# 05_Output_Connectors.net
KiCad netlist of a schematic drawn in Altium Designer
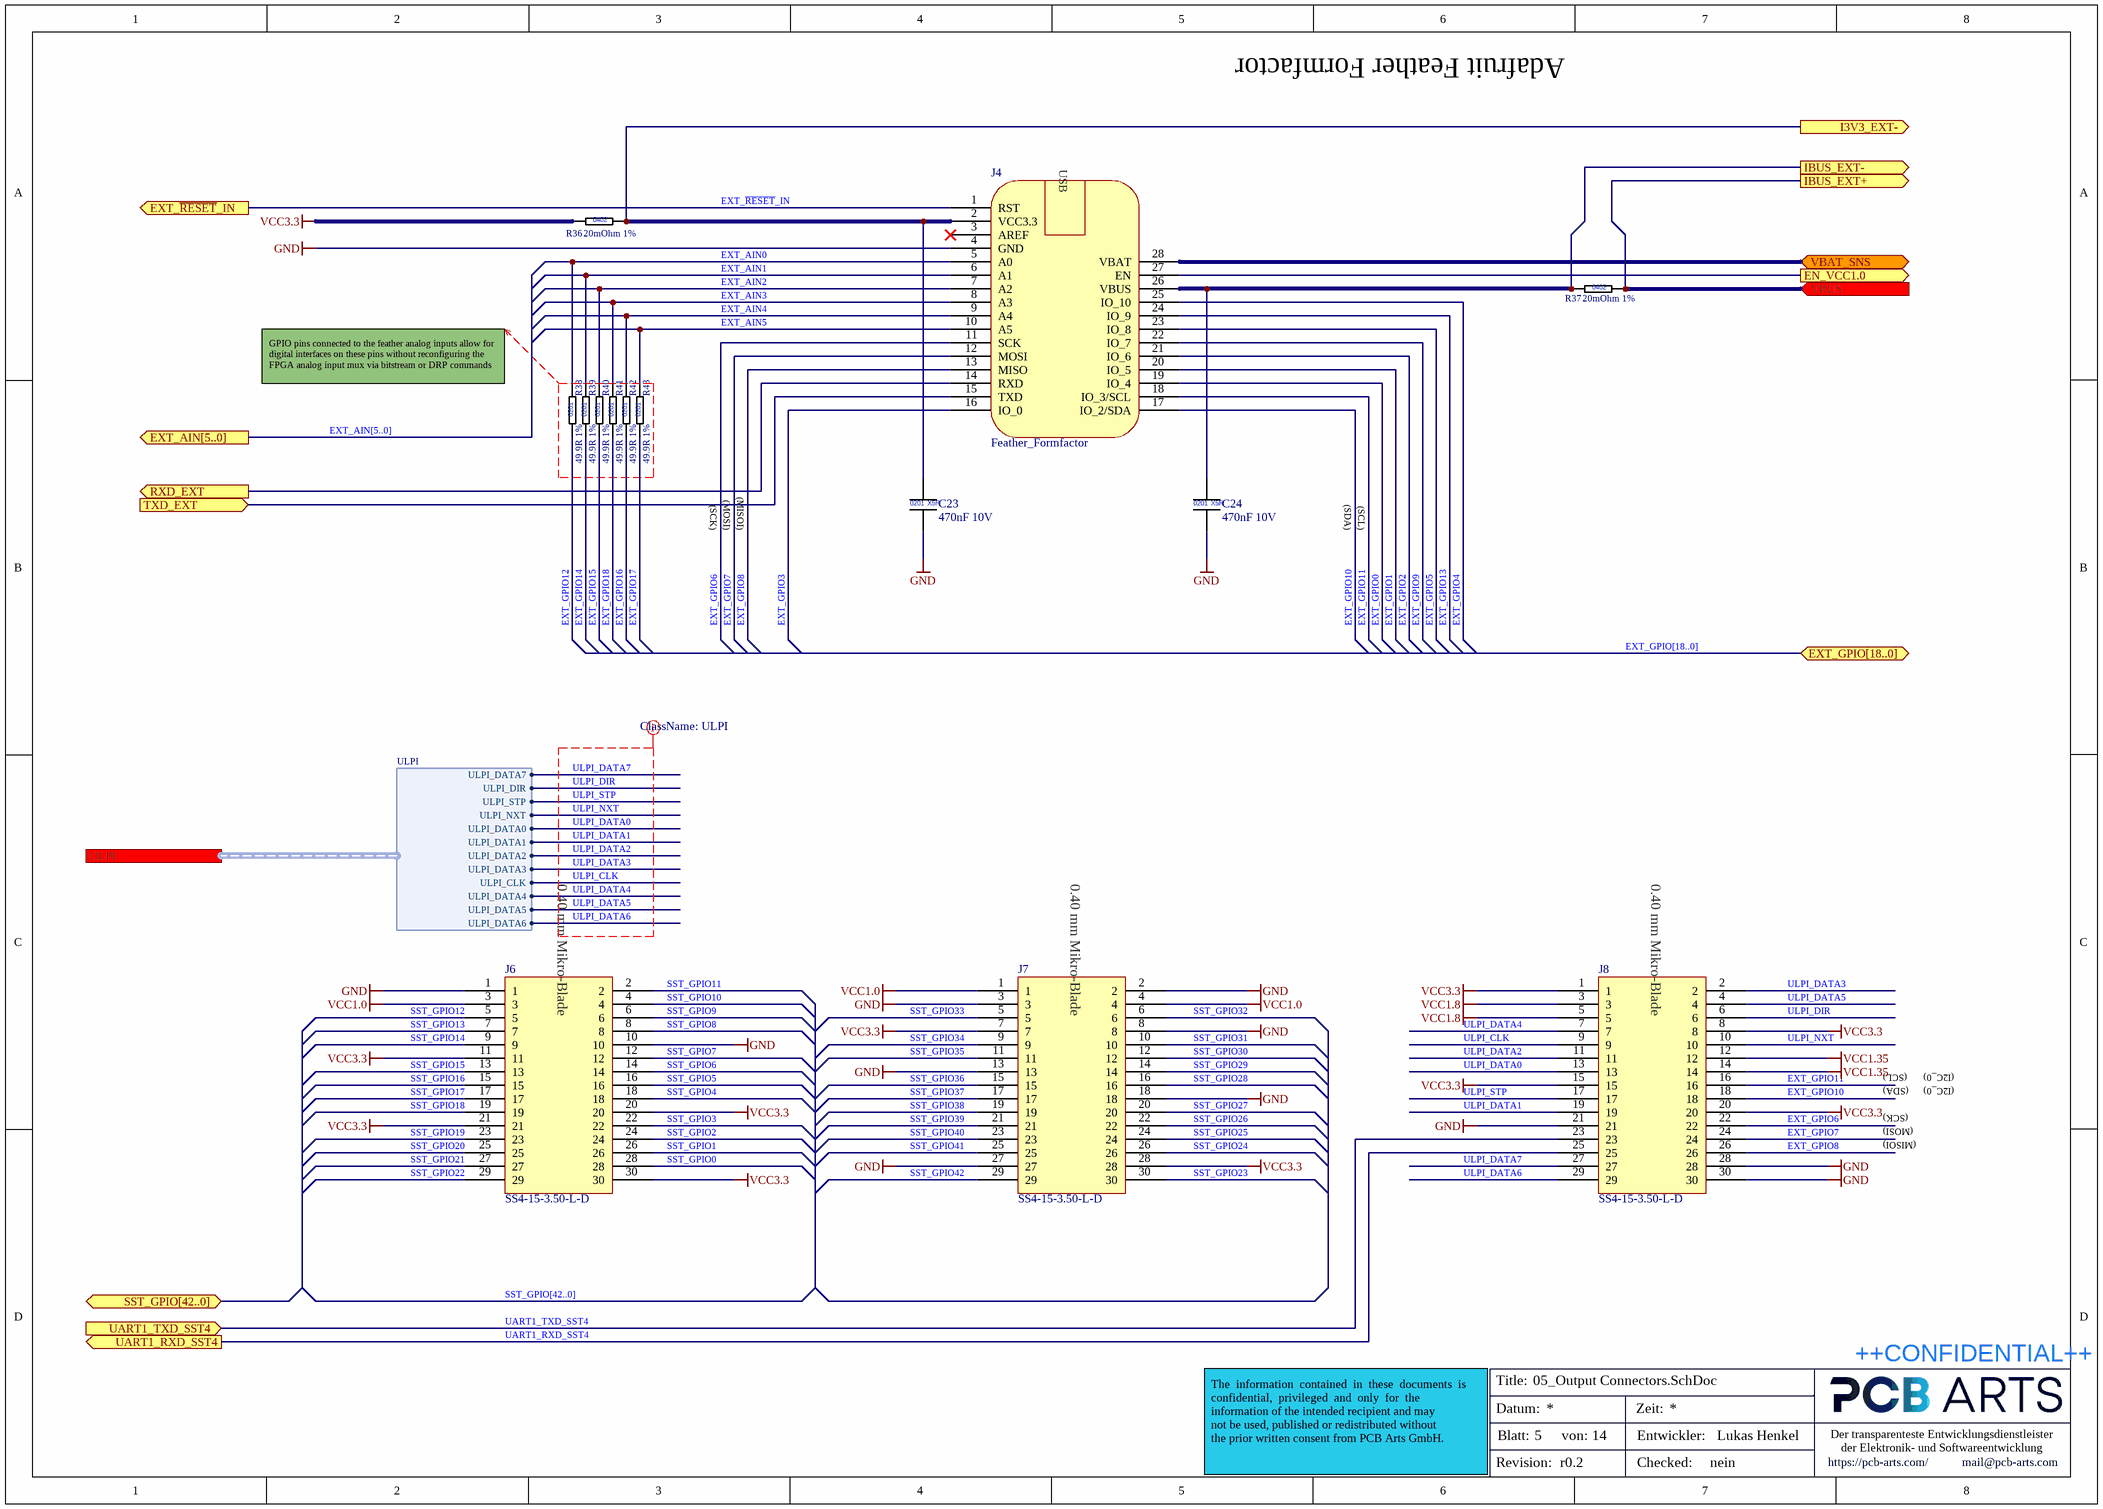
[diagram p0: 05_Output Connectors.SchDoc]

(export (version "E")
  (design (tool "Eeschema 10.0.6"))
  (components
    (comp (ref "C23")
      (value "470nF 10V")
      (footprint "Zynq-Feather-HD:CAPC0603X03L")
      (description "Multilayer Ceramic Capacitors MLCC - SMD/SMT 0201 10VDC")
      (libsource (lib "Zynq-Feather-HD") (part "CAP_0201_470nF_10V"))
    )
    (comp (ref "C24")
      (value "470nF 10V")
      (footprint "Zynq-Feather-HD:CAPC0603X03L")
      (description "Multilayer Ceramic Capacitors MLCC - SMD/SMT 0201 10VDC")
      (libsource (lib "Zynq-Feather-HD") (part "CAP_0201_470nF_10V"))
    )
    (comp (ref "J4")
      (value "Feather_Formfactor")
      (footprint "Zynq-Feather-HD:Feather_FFC")
      (libsource (lib "Zynq-Feather-HD") (part "Feather_Formfactor"))
    )
    (comp (ref "J6")
      (value "SS4-15-3.50-L-D")
      (footprint "Zynq-Feather-HD:SS4-15-3.50-L-D")
      (description "0.40 mm Mikro-Blade & Beam ultrafeine Raster-Stiftleiste")
      (libsource (lib "Zynq-Feather-HD") (part "SS4-15-3.50-L-D_0.40 mm Mikro-Blade & Beam"))
    )
    (comp (ref "J7")
      (value "SS4-15-3.50-L-D")
      (footprint "Zynq-Feather-HD:SS4-15-3.50-L-D")
      (description "0.40 mm Mikro-Blade & Beam ultrafeine Raster-Stiftleiste")
      (libsource (lib "Zynq-Feather-HD") (part "SS4-15-3.50-L-D_0.40 mm Mikro-Blade & Beam"))
    )
    (comp (ref "J8")
      (value "SS4-15-3.50-L-D")
      (footprint "Zynq-Feather-HD:SS4-15-3.50-L-D")
      (description "0.40 mm Mikro-Blade & Beam ultrafeine Raster-Stiftleiste")
      (libsource (lib "Zynq-Feather-HD") (part "SS4-15-3.50-L-D_0.40 mm Mikro-Blade & Beam"))
    )
    (comp (ref "R36")
      (value "20mOhm 1%")
      (footprint "Zynq-Feather-HD:RESC1005X04L")
      (description "Thick Film Resistors - SMD 20mOHM 1%")
      (libsource (lib "Zynq-Feather-HD") (part "RES_0402_20mR_1%"))
    )
    (comp (ref "R37")
      (value "20mOhm 1%")
      (footprint "Zynq-Feather-HD:RESC1005X04L")
      (description "Thick Film Resistors - SMD 20mOHM 1%")
      (libsource (lib "Zynq-Feather-HD") (part "RES_0402_20mR_1%"))
    )
    (comp (ref "R38")
      (value "49.9R 1%")
      (footprint "Zynq-Feather-HD:RESC0603X03L")
      (description "Thick Film Resistors - SMD 49.9R OHM 1%")
      (libsource (lib "Zynq-Feather-HD") (part "RES_0201_49.9R_1%"))
    )
    (comp (ref "R39")
      (value "49.9R 1%")
      (footprint "Zynq-Feather-HD:RESC0603X03L")
      (description "Thick Film Resistors - SMD 49.9R OHM 1%")
      (libsource (lib "Zynq-Feather-HD") (part "RES_0201_49.9R_1%"))
    )
    (comp (ref "R40")
      (value "49.9R 1%")
      (footprint "Zynq-Feather-HD:RESC0603X03L")
      (description "Thick Film Resistors - SMD 49.9R OHM 1%")
      (libsource (lib "Zynq-Feather-HD") (part "RES_0201_49.9R_1%"))
    )
    (comp (ref "R41")
      (value "49.9R 1%")
      (footprint "Zynq-Feather-HD:RESC0603X03L")
      (description "Thick Film Resistors - SMD 49.9R OHM 1%")
      (libsource (lib "Zynq-Feather-HD") (part "RES_0201_49.9R_1%"))
    )
    (comp (ref "R42")
      (value "49.9R 1%")
      (footprint "Zynq-Feather-HD:RESC0603X03L")
      (description "Thick Film Resistors - SMD 49.9R OHM 1%")
      (libsource (lib "Zynq-Feather-HD") (part "RES_0201_49.9R_1%"))
    )
    (comp (ref "R43")
      (value "49.9R 1%")
      (footprint "Zynq-Feather-HD:RESC0603X03L")
      (description "Thick Film Resistors - SMD 49.9R OHM 1%")
      (libsource (lib "Zynq-Feather-HD") (part "RES_0201_49.9R_1%"))
    )
  )
  (nets
    (net (code "2") (name "/EN_VCC1.0") (class "Default")
      (node (ref "J4") (pin "27") (pinfunction "EN_27") (pintype "passive"))
    )
    (net (code "3") (name "/EXT_AIN0") (class "Default")
      (node (ref "J4") (pin "5") (pinfunction "A0_5") (pintype "passive"))
      (node (ref "R38") (pin "2") (pinfunction "2_2") (pintype "passive"))
    )
    (net (code "4") (name "/EXT_AIN1") (class "Default")
      (node (ref "J4") (pin "6") (pinfunction "A1_6") (pintype "passive"))
      (node (ref "R39") (pin "2") (pinfunction "2_2") (pintype "passive"))
    )
    (net (code "5") (name "/EXT_AIN2") (class "Default")
      (node (ref "J4") (pin "7") (pinfunction "A2_7") (pintype "passive"))
      (node (ref "R40") (pin "2") (pinfunction "2_2") (pintype "passive"))
    )
    (net (code "6") (name "/EXT_AIN3") (class "Default")
      (node (ref "J4") (pin "8") (pinfunction "A3_8") (pintype "passive"))
      (node (ref "R41") (pin "2") (pinfunction "2_2") (pintype "passive"))
    )
    (net (code "7") (name "/EXT_AIN4") (class "Default")
      (node (ref "J4") (pin "9") (pinfunction "A4_9") (pintype "passive"))
      (node (ref "R42") (pin "2") (pinfunction "2_2") (pintype "passive"))
    )
    (net (code "8") (name "/EXT_AIN5") (class "Default")
      (node (ref "J4") (pin "10") (pinfunction "A5_10") (pintype "passive"))
      (node (ref "R43") (pin "2") (pinfunction "2_2") (pintype "passive"))
    )
    (net (code "10") (name "/EXT_GPIO0") (class "Default")
      (node (ref "J4") (pin "19") (pinfunction "IO_4_19") (pintype "passive"))
    )
    (net (code "11") (name "/EXT_GPIO1") (class "Default")
      (node (ref "J4") (pin "20") (pinfunction "IO_5_20") (pintype "passive"))
    )
    (net (code "12") (name "/EXT_GPIO2") (class "Default")
      (node (ref "J4") (pin "21") (pinfunction "IO_6_21") (pintype "passive"))
    )
    (net (code "13") (name "/EXT_GPIO3") (class "Default")
      (node (ref "J4") (pin "16") (pinfunction "IO_0_16") (pintype "passive"))
    )
    (net (code "14") (name "/EXT_GPIO4") (class "Default")
      (node (ref "J4") (pin "25") (pinfunction "IO_10_25") (pintype "passive"))
    )
    (net (code "15") (name "/EXT_GPIO5") (class "Default")
      (node (ref "J4") (pin "23") (pinfunction "IO_8_23") (pintype "passive"))
    )
    (net (code "16") (name "/EXT_GPIO6") (class "Default")
      (node (ref "J4") (pin "11") (pinfunction "SCK_11") (pintype "passive"))
      (node (ref "J8") (pin "22") (pinfunction "22_22") (pintype "passive"))
    )
    (net (code "17") (name "/EXT_GPIO7") (class "Default")
      (node (ref "J4") (pin "12") (pinfunction "MOSI_12") (pintype "passive"))
      (node (ref "J8") (pin "24") (pinfunction "24_24") (pintype "passive"))
    )
    (net (code "18") (name "/EXT_GPIO8") (class "Default")
      (node (ref "J4") (pin "13") (pinfunction "MISO_13") (pintype "passive"))
      (node (ref "J8") (pin "26") (pinfunction "26_26") (pintype "passive"))
    )
    (net (code "19") (name "/EXT_GPIO9") (class "Default")
      (node (ref "J4") (pin "22") (pinfunction "IO_7_22") (pintype "passive"))
    )
    (net (code "20") (name "/EXT_GPIO10") (class "Default")
      (node (ref "J4") (pin "17") (pinfunction "IO_2/SDA_17") (pintype "passive"))
      (node (ref "J8") (pin "18") (pinfunction "18_18") (pintype "passive"))
    )
    (net (code "21") (name "/EXT_GPIO11") (class "Default")
      (node (ref "J4") (pin "18") (pinfunction "IO_3/SCL_18") (pintype "passive"))
      (node (ref "J8") (pin "16") (pinfunction "16_16") (pintype "passive"))
    )
    (net (code "22") (name "/EXT_GPIO12") (class "Default")
      (node (ref "R38") (pin "1") (pinfunction "1_1") (pintype "passive"))
    )
    (net (code "23") (name "/EXT_GPIO13") (class "Default")
      (node (ref "J4") (pin "24") (pinfunction "IO_9_24") (pintype "passive"))
    )
    (net (code "24") (name "/EXT_GPIO14") (class "Default")
      (node (ref "R39") (pin "1") (pinfunction "1_1") (pintype "passive"))
    )
    (net (code "25") (name "/EXT_GPIO15") (class "Default")
      (node (ref "R40") (pin "1") (pinfunction "1_1") (pintype "passive"))
    )
    (net (code "26") (name "/EXT_GPIO16") (class "Default")
      (node (ref "R42") (pin "1") (pinfunction "1_1") (pintype "passive"))
    )
    (net (code "27") (name "/EXT_GPIO17") (class "Default")
      (node (ref "R43") (pin "1") (pinfunction "1_1") (pintype "passive"))
    )
    (net (code "28") (name "/EXT_GPIO18") (class "Default")
      (node (ref "R41") (pin "1") (pinfunction "1_1") (pintype "passive"))
    )
    (net (code "30") (name "/EXT_~{RESET}_IN") (class "Default")
      (node (ref "J4") (pin "1") (pinfunction "RST_1") (pintype "passive"))
    )
    (net (code "31") (name "/I3V3_EXT-") (class "Default")
      (node (ref "C23") (pin "1") (pinfunction "1_1") (pintype "passive"))
      (node (ref "J4") (pin "2") (pinfunction "VCC3.3_2") (pintype "passive"))
      (node (ref "R36") (pin "2") (pinfunction "2_2") (pintype "passive"))
    )
    (net (code "32") (name "/IBUS_EXT+") (class "Default")
      (node (ref "R37") (pin "2") (pinfunction "2_2") (pintype "passive"))
    )
    (net (code "33") (name "/IBUS_EXT-") (class "Default")
      (node (ref "C24") (pin "1") (pinfunction "1_1") (pintype "passive"))
      (node (ref "J4") (pin "26") (pinfunction "VBUS_26") (pintype "passive"))
      (node (ref "R37") (pin "1") (pinfunction "1_1") (pintype "passive"))
    )
    (net (code "34") (name "/RXD_EXT") (class "Default")
      (node (ref "J4") (pin "14") (pinfunction "RXD_14") (pintype "passive"))
    )
    (net (code "35") (name "/SST_GPIO0") (class "Default")
      (node (ref "J6") (pin "28") (pinfunction "28_28") (pintype "passive"))
    )
    (net (code "36") (name "/SST_GPIO1") (class "Default")
      (node (ref "J6") (pin "26") (pinfunction "26_26") (pintype "passive"))
    )
    (net (code "37") (name "/SST_GPIO2") (class "Default")
      (node (ref "J6") (pin "24") (pinfunction "24_24") (pintype "passive"))
    )
    (net (code "38") (name "/SST_GPIO3") (class "Default")
      (node (ref "J6") (pin "22") (pinfunction "22_22") (pintype "passive"))
    )
    (net (code "39") (name "/SST_GPIO4") (class "Default")
      (node (ref "J6") (pin "18") (pinfunction "18_18") (pintype "passive"))
    )
    (net (code "40") (name "/SST_GPIO5") (class "Default")
      (node (ref "J6") (pin "16") (pinfunction "16_16") (pintype "passive"))
    )
    (net (code "41") (name "/SST_GPIO6") (class "Default")
      (node (ref "J6") (pin "14") (pinfunction "14_14") (pintype "passive"))
    )
    (net (code "42") (name "/SST_GPIO7") (class "Default")
      (node (ref "J6") (pin "12") (pinfunction "12_12") (pintype "passive"))
    )
    (net (code "43") (name "/SST_GPIO8") (class "Default")
      (node (ref "J6") (pin "8") (pinfunction "8_8") (pintype "passive"))
    )
    (net (code "44") (name "/SST_GPIO9") (class "Default")
      (node (ref "J6") (pin "6") (pinfunction "6_6") (pintype "passive"))
    )
    (net (code "45") (name "/SST_GPIO10") (class "Default")
      (node (ref "J6") (pin "4") (pinfunction "4_4") (pintype "passive"))
    )
    (net (code "46") (name "/SST_GPIO11") (class "Default")
      (node (ref "J6") (pin "2") (pinfunction "2_2") (pintype "passive"))
    )
    (net (code "47") (name "/SST_GPIO12") (class "Default")
      (node (ref "J6") (pin "5") (pinfunction "5_5") (pintype "passive"))
    )
    (net (code "48") (name "/SST_GPIO13") (class "Default")
      (node (ref "J6") (pin "7") (pinfunction "7_7") (pintype "passive"))
    )
    (net (code "49") (name "/SST_GPIO14") (class "Default")
      (node (ref "J6") (pin "9") (pinfunction "9_9") (pintype "passive"))
    )
    (net (code "50") (name "/SST_GPIO15") (class "Default")
      (node (ref "J6") (pin "13") (pinfunction "13_13") (pintype "passive"))
    )
    (net (code "51") (name "/SST_GPIO16") (class "Default")
      (node (ref "J6") (pin "15") (pinfunction "15_15") (pintype "passive"))
    )
    (net (code "52") (name "/SST_GPIO17") (class "Default")
      (node (ref "J6") (pin "17") (pinfunction "17_17") (pintype "passive"))
    )
    (net (code "53") (name "/SST_GPIO18") (class "Default")
      (node (ref "J6") (pin "19") (pinfunction "19_19") (pintype "passive"))
    )
    (net (code "54") (name "/SST_GPIO19") (class "Default")
      (node (ref "J6") (pin "23") (pinfunction "23_23") (pintype "passive"))
    )
    (net (code "55") (name "/SST_GPIO20") (class "Default")
      (node (ref "J6") (pin "25") (pinfunction "25_25") (pintype "passive"))
    )
    (net (code "56") (name "/SST_GPIO21") (class "Default")
      (node (ref "J6") (pin "27") (pinfunction "27_27") (pintype "passive"))
    )
    (net (code "57") (name "/SST_GPIO22") (class "Default")
      (node (ref "J6") (pin "29") (pinfunction "29_29") (pintype "passive"))
    )
    (net (code "58") (name "/SST_GPIO23") (class "Default")
      (node (ref "J7") (pin "30") (pinfunction "30_30") (pintype "passive"))
    )
    (net (code "59") (name "/SST_GPIO24") (class "Default")
      (node (ref "J7") (pin "26") (pinfunction "26_26") (pintype "passive"))
    )
    (net (code "60") (name "/SST_GPIO25") (class "Default")
      (node (ref "J7") (pin "24") (pinfunction "24_24") (pintype "passive"))
    )
    (net (code "61") (name "/SST_GPIO26") (class "Default")
      (node (ref "J7") (pin "22") (pinfunction "22_22") (pintype "passive"))
    )
    (net (code "62") (name "/SST_GPIO27") (class "Default")
      (node (ref "J7") (pin "20") (pinfunction "20_20") (pintype "passive"))
    )
    (net (code "63") (name "/SST_GPIO28") (class "Default")
      (node (ref "J7") (pin "16") (pinfunction "16_16") (pintype "passive"))
    )
    (net (code "64") (name "/SST_GPIO29") (class "Default")
      (node (ref "J7") (pin "14") (pinfunction "14_14") (pintype "passive"))
    )
    (net (code "65") (name "/SST_GPIO30") (class "Default")
      (node (ref "J7") (pin "12") (pinfunction "12_12") (pintype "passive"))
    )
    (net (code "66") (name "/SST_GPIO31") (class "Default")
      (node (ref "J7") (pin "10") (pinfunction "10_10") (pintype "passive"))
    )
    (net (code "67") (name "/SST_GPIO32") (class "Default")
      (node (ref "J7") (pin "6") (pinfunction "6_6") (pintype "passive"))
    )
    (net (code "68") (name "/SST_GPIO33") (class "Default")
      (node (ref "J7") (pin "5") (pinfunction "5_5") (pintype "passive"))
    )
    (net (code "69") (name "/SST_GPIO34") (class "Default")
      (node (ref "J7") (pin "9") (pinfunction "9_9") (pintype "passive"))
    )
    (net (code "70") (name "/SST_GPIO35") (class "Default")
      (node (ref "J7") (pin "11") (pinfunction "11_11") (pintype "passive"))
    )
    (net (code "71") (name "/SST_GPIO36") (class "Default")
      (node (ref "J7") (pin "15") (pinfunction "15_15") (pintype "passive"))
    )
    (net (code "72") (name "/SST_GPIO37") (class "Default")
      (node (ref "J7") (pin "17") (pinfunction "17_17") (pintype "passive"))
    )
    (net (code "73") (name "/SST_GPIO38") (class "Default")
      (node (ref "J7") (pin "19") (pinfunction "19_19") (pintype "passive"))
    )
    (net (code "74") (name "/SST_GPIO39") (class "Default")
      (node (ref "J7") (pin "21") (pinfunction "21_21") (pintype "passive"))
    )
    (net (code "75") (name "/SST_GPIO40") (class "Default")
      (node (ref "J7") (pin "23") (pinfunction "23_23") (pintype "passive"))
    )
    (net (code "76") (name "/SST_GPIO41") (class "Default")
      (node (ref "J7") (pin "25") (pinfunction "25_25") (pintype "passive"))
    )
    (net (code "77") (name "/SST_GPIO42") (class "Default")
      (node (ref "J7") (pin "29") (pinfunction "29_29") (pintype "passive"))
    )
    (net (code "79") (name "/TXD_EXT") (class "Default")
      (node (ref "J4") (pin "15") (pinfunction "TXD_15") (pintype "passive"))
    )
    (net (code "80") (name "/UART1_RXD_SST4") (class "Default")
      (node (ref "J8") (pin "25") (pinfunction "25_25") (pintype "passive"))
    )
    (net (code "81") (name "/UART1_TXD_SST4") (class "Default")
      (node (ref "J8") (pin "23") (pinfunction "23_23") (pintype "passive"))
    )
    (net (code "82") (name "/ULPI_CLK") (class "Default")
      (node (ref "J8") (pin "9") (pinfunction "9_9") (pintype "passive"))
    )
    (net (code "83") (name "/ULPI_DATA0") (class "Default")
      (node (ref "J8") (pin "13") (pinfunction "13_13") (pintype "passive"))
    )
    (net (code "84") (name "/ULPI_DATA1") (class "Default")
      (node (ref "J8") (pin "19") (pinfunction "19_19") (pintype "passive"))
    )
    (net (code "85") (name "/ULPI_DATA2") (class "Default")
      (node (ref "J8") (pin "11") (pinfunction "11_11") (pintype "passive"))
    )
    (net (code "86") (name "/ULPI_DATA3") (class "Default")
      (node (ref "J8") (pin "2") (pinfunction "2_2") (pintype "passive"))
    )
    (net (code "87") (name "/ULPI_DATA4") (class "Default")
      (node (ref "J8") (pin "7") (pinfunction "7_7") (pintype "passive"))
    )
    (net (code "88") (name "/ULPI_DATA5") (class "Default")
      (node (ref "J8") (pin "4") (pinfunction "4_4") (pintype "passive"))
    )
    (net (code "89") (name "/ULPI_DATA6") (class "Default")
      (node (ref "J8") (pin "29") (pinfunction "29_29") (pintype "passive"))
    )
    (net (code "90") (name "/ULPI_DATA7") (class "Default")
      (node (ref "J8") (pin "27") (pinfunction "27_27") (pintype "passive"))
    )
    (net (code "91") (name "/ULPI_DIR") (class "Default")
      (node (ref "J8") (pin "6") (pinfunction "6_6") (pintype "passive"))
    )
    (net (code "92") (name "/ULPI_NXT") (class "Default")
      (node (ref "J8") (pin "10") (pinfunction "10_10") (pintype "passive"))
    )
    (net (code "93") (name "/ULPI_STP") (class "Default")
      (node (ref "J8") (pin "17") (pinfunction "17_17") (pintype "passive"))
    )
    (net (code "94") (name "/VBAT_SNS") (class "Default")
      (node (ref "J4") (pin "28") (pinfunction "VBAT_28") (pintype "passive"))
    )
    (net (code "96") (name "GND") (class "Default")
      (node (ref "C23") (pin "2") (pinfunction "2_2") (pintype "passive"))
      (node (ref "C24") (pin "2") (pinfunction "2_2") (pintype "passive"))
      (node (ref "J4") (pin "4") (pinfunction "GND_4") (pintype "passive"))
      (node (ref "J6") (pin "1") (pinfunction "1_1") (pintype "passive"))
      (node (ref "J6") (pin "10") (pinfunction "10_10") (pintype "passive"))
      (node (ref "J7") (pin "13") (pinfunction "13_13") (pintype "passive"))
      (node (ref "J7") (pin "18") (pinfunction "18_18") (pintype "passive"))
      (node (ref "J7") (pin "2") (pinfunction "2_2") (pintype "passive"))
      (node (ref "J7") (pin "27") (pinfunction "27_27") (pintype "passive"))
      (node (ref "J7") (pin "3") (pinfunction "3_3") (pintype "passive"))
      (node (ref "J7") (pin "8") (pinfunction "8_8") (pintype "passive"))
      (node (ref "J8") (pin "21") (pinfunction "21_21") (pintype "passive"))
      (node (ref "J8") (pin "28") (pinfunction "28_28") (pintype "passive"))
      (node (ref "J8") (pin "30") (pinfunction "30_30") (pintype "passive"))
    )
    (net (code "97") (name "VCC1.0") (class "Default")
      (node (ref "J6") (pin "3") (pinfunction "3_3") (pintype "passive"))
      (node (ref "J7") (pin "1") (pinfunction "1_1") (pintype "passive"))
      (node (ref "J7") (pin "4") (pinfunction "4_4") (pintype "passive"))
    )
    (net (code "98") (name "VCC1.8") (class "Default")
      (node (ref "J8") (pin "3") (pinfunction "3_3") (pintype "passive"))
      (node (ref "J8") (pin "5") (pinfunction "5_5") (pintype "passive"))
    )
    (net (code "99") (name "VCC1.35") (class "Default")
      (node (ref "J8") (pin "12") (pinfunction "12_12") (pintype "passive"))
      (node (ref "J8") (pin "14") (pinfunction "14_14") (pintype "passive"))
    )
    (net (code "100") (name "VCC3.3") (class "Default")
      (node (ref "J6") (pin "11") (pinfunction "11_11") (pintype "passive"))
      (node (ref "J6") (pin "20") (pinfunction "20_20") (pintype "passive"))
      (node (ref "J6") (pin "21") (pinfunction "21_21") (pintype "passive"))
      (node (ref "J6") (pin "30") (pinfunction "30_30") (pintype "passive"))
      (node (ref "J7") (pin "28") (pinfunction "28_28") (pintype "passive"))
      (node (ref "J7") (pin "7") (pinfunction "7_7") (pintype "passive"))
      (node (ref "J8") (pin "1") (pinfunction "1_1") (pintype "passive"))
      (node (ref "J8") (pin "15") (pinfunction "15_15") (pintype "passive"))
      (node (ref "J8") (pin "20") (pinfunction "20_20") (pintype "passive"))
      (node (ref "J8") (pin "8") (pinfunction "8_8") (pintype "passive"))
      (node (ref "R36") (pin "1") (pinfunction "1_1") (pintype "passive"))
    )
    (net (code "101") (name "unconnected-(J4-AREF-Pad3)") (class "Default")
      (node (ref "J4") (pin "3") (pinfunction "AREF_3") (pintype "passive+no_connect"))
    )
  )
)
